# spiceconvert.net
KiCad netlist of a schematic drawn in EAGLE
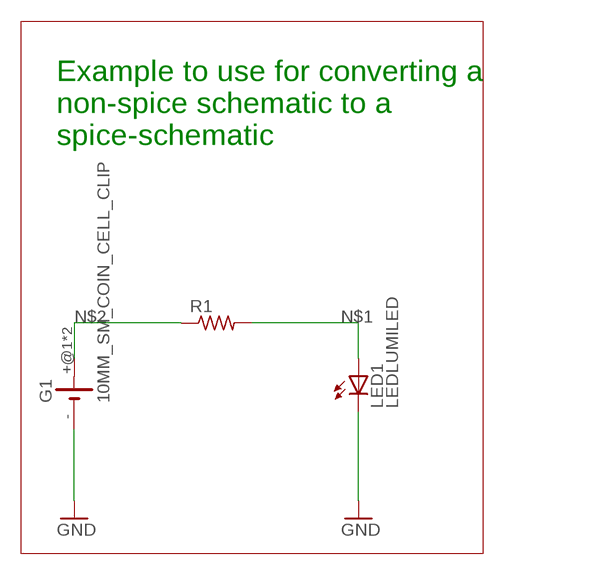
[diagram p0: schematic, sheet 1]

(export (version "E")
  (design (tool "Eeschema 10.0.6"))
  (components
    (comp (ref "G1")
      (value "10MM_SM_COIN_CELL_CLIP")
      (footprint "eagle-import:10MM_SM_COIN_CELL_CLIP")
      (libsource (lib "eagle-import") (part "10MM_SM_COIN_CELL_CLIP"))
    )
    (comp (ref "LED1")
      (value "LEDLUMILED")
      (footprint "eagle-import:LUMILED")
      (libsource (lib "eagle-import") (part "LEDLUMILED"))
    )
    (comp (ref "R1")
      (value "R-US_0207/10")
      (footprint "eagle-import:0207_10")
      (libsource (lib "eagle-import") (part "R-US_0207/10"))
    )
  )
  (nets
    (net (code "1") (name "/N$1") (class "Default")
      (node (ref "LED1") (pin "2+") (pinfunction "A_2+") (pintype "passive"))
      (node (ref "R1") (pin "2") (pinfunction "2_2") (pintype "passive"))
    )
    (net (code "2") (name "/N$2") (class "Default")
      (node (ref "G1") (pin "+@1") (pinfunction "+_+@1") (pintype "passive"))
      (node (ref "G1") (pin "+@2") (pinfunction "+_+@2") (pintype "passive"))
      (node (ref "R1") (pin "1") (pinfunction "1_1") (pintype "passive"))
    )
    (net (code "3") (name "GND") (class "Default")
      (node (ref "G1") (pin "-") (pinfunction "-_-") (pintype "passive"))
      (node (ref "LED1") (pin "4-") (pinfunction "C_4-") (pintype "passive"))
    )
  )
)
